# stm_ucboard.net
KiCad netlist of a schematic drawn in EAGLE
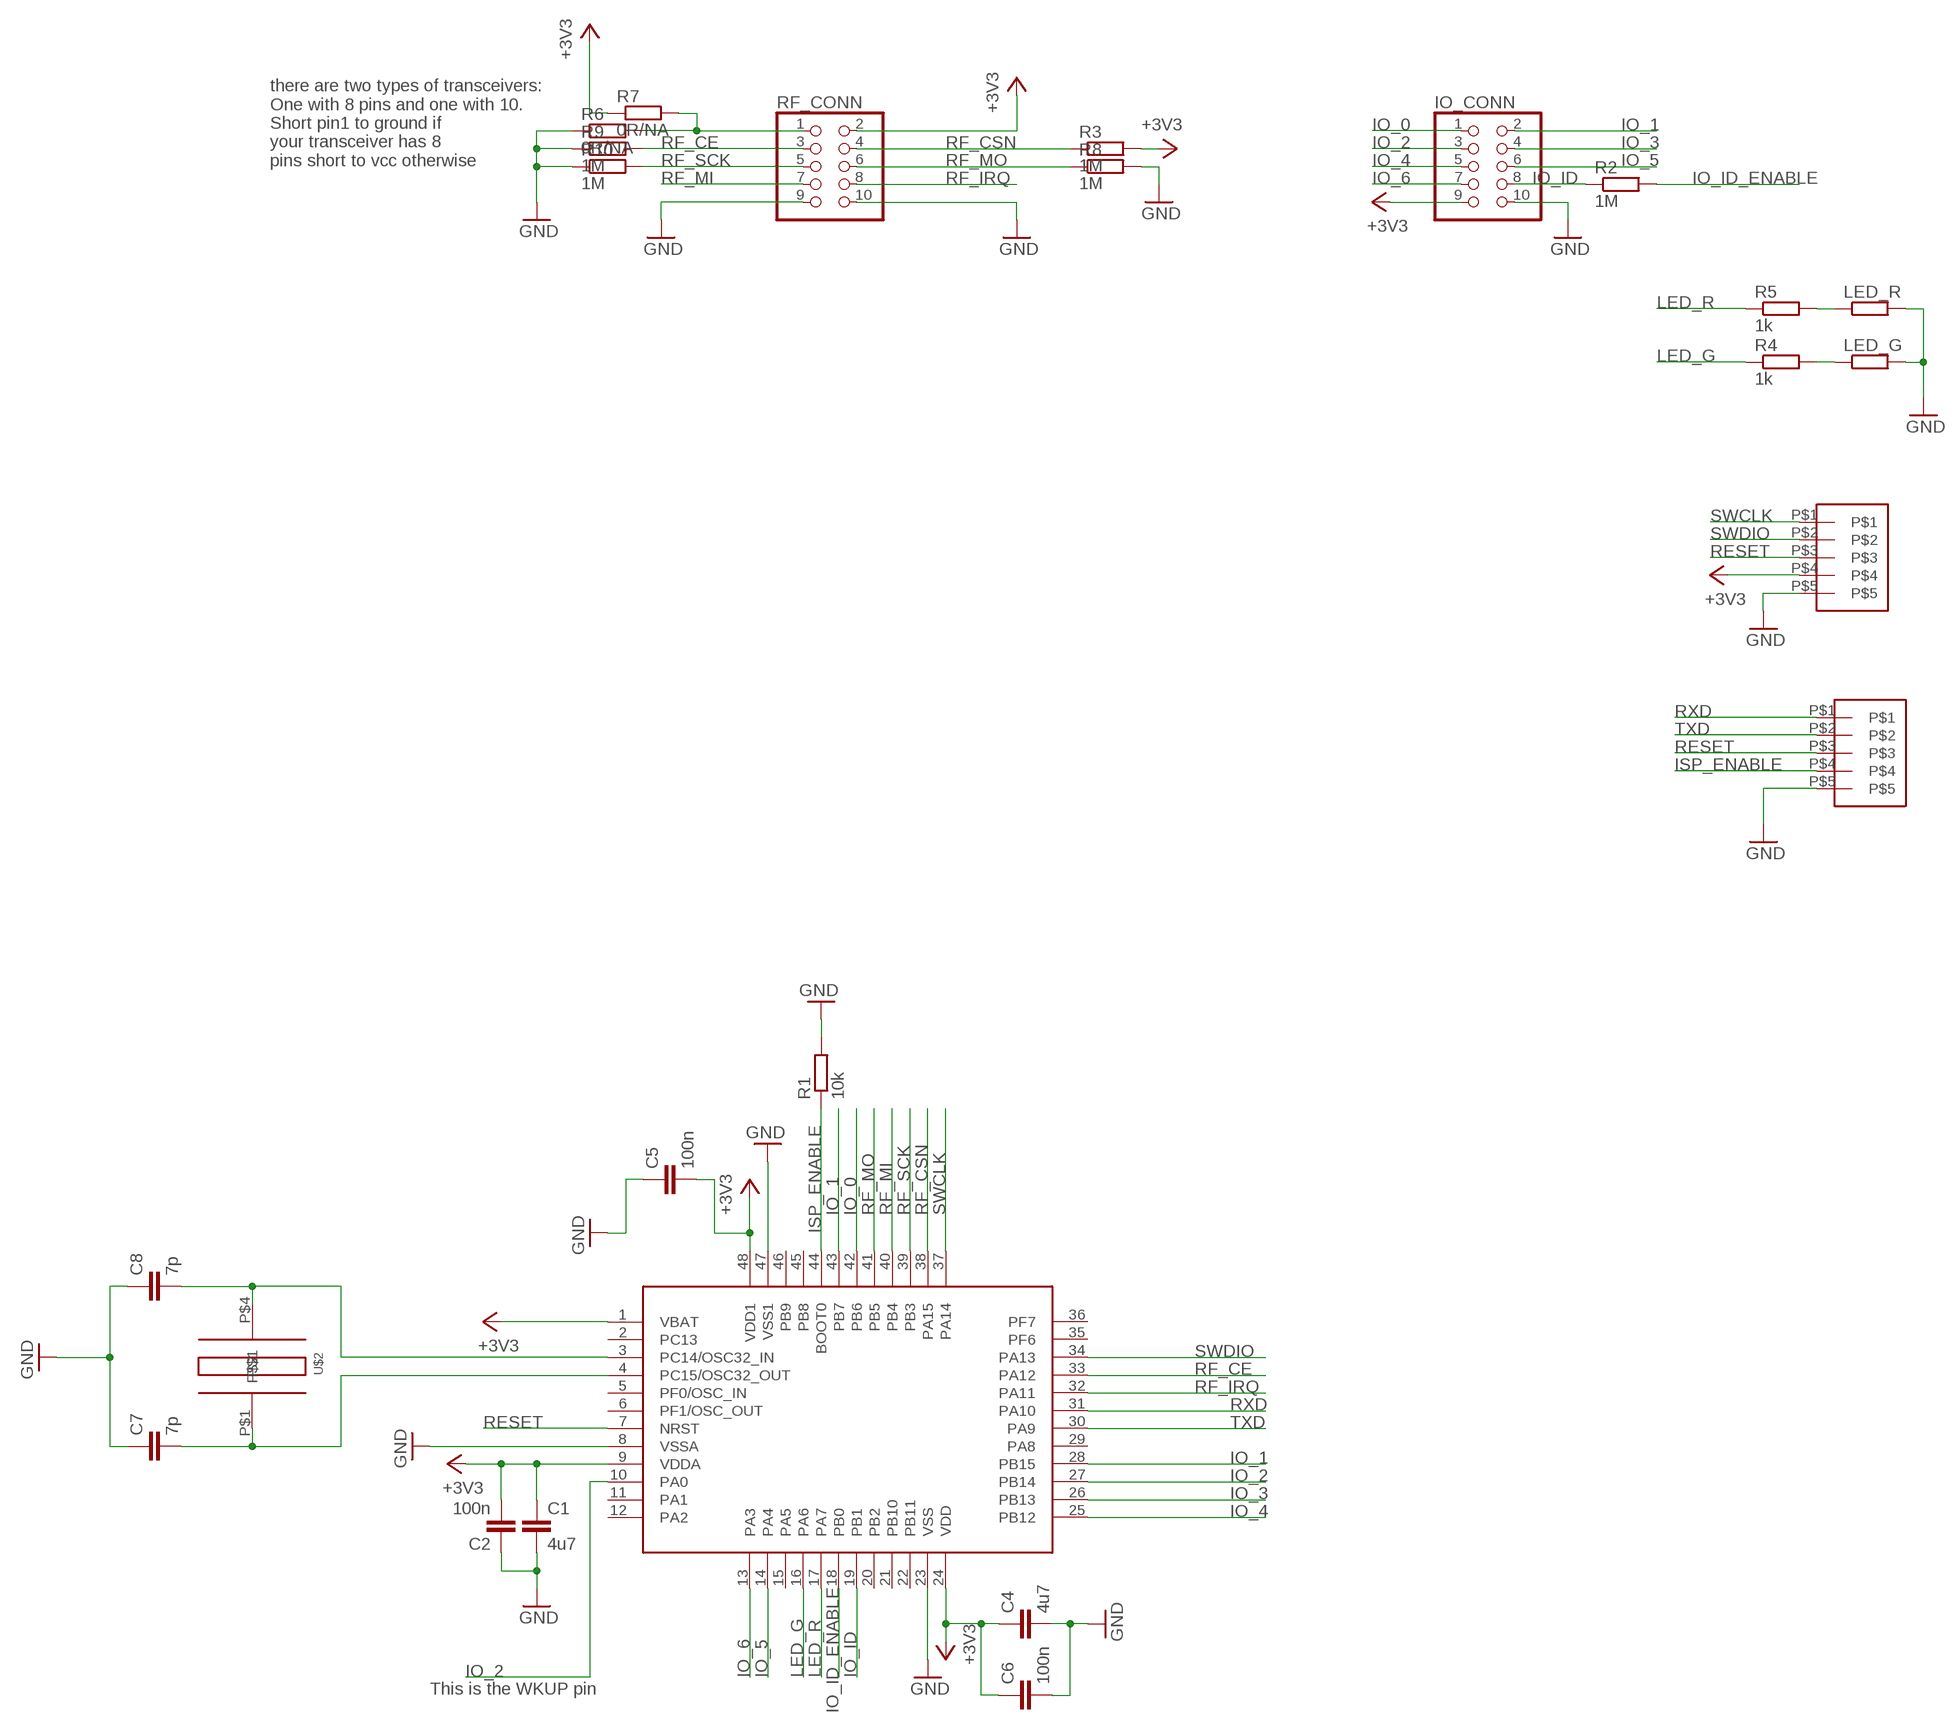
[diagram p0: schematic, sheet 1]

(export (version "E")
  (design (tool "Eeschema 10.0.6"))
  (components
    (comp (ref "C1")
      (value "4u7")
      (footprint "eagle-import:C0603")
      (libsource (lib "eagle-import") (part "C-EUC0603"))
    )
    (comp (ref "C2")
      (value "100n")
      (footprint "eagle-import:C0603")
      (libsource (lib "eagle-import") (part "C-EUC0603"))
    )
    (comp (ref "C4")
      (value "4u7")
      (footprint "eagle-import:C0603")
      (libsource (lib "eagle-import") (part "C-EUC0603"))
    )
    (comp (ref "C5")
      (value "100n")
      (footprint "eagle-import:C0603")
      (libsource (lib "eagle-import") (part "C-EUC0603"))
    )
    (comp (ref "C6")
      (value "100n")
      (footprint "eagle-import:C0603")
      (libsource (lib "eagle-import") (part "C-EUC0603"))
    )
    (comp (ref "C7")
      (value "7p")
      (footprint "eagle-import:C0603")
      (libsource (lib "eagle-import") (part "C-EUC0603"))
    )
    (comp (ref "C8")
      (value "7p")
      (footprint "eagle-import:C0603")
      (libsource (lib "eagle-import") (part "C-EUC0603"))
    )
    (comp (ref "DBG")
      (value "005CONTACTS")
      (footprint "eagle-import:05HEADER")
      (libsource (lib "eagle-import") (part "005CONTACTS"))
    )
    (comp (ref "IO_CONN")
      (value "PINHD-2X5")
      (footprint "eagle-import:2X05")
      (libsource (lib "eagle-import") (part "PINHD-2X5"))
    )
    (comp (ref "LED_G")
      (value "R-EU_R0402")
      (footprint "eagle-import:R0402")
      (libsource (lib "eagle-import") (part "R-EU_R0402"))
    )
    (comp (ref "LED_R")
      (value "R-EU_R0402")
      (footprint "eagle-import:R0402")
      (libsource (lib "eagle-import") (part "R-EU_R0402"))
    )
    (comp (ref "R1")
      (value "10k")
      (footprint "eagle-import:R0402")
      (libsource (lib "eagle-import") (part "R-EU_R0402"))
    )
    (comp (ref "R2")
      (value "1M")
      (footprint "eagle-import:R0402")
      (libsource (lib "eagle-import") (part "R-EU_R0402"))
    )
    (comp (ref "R3")
      (value "1M")
      (footprint "eagle-import:R0402")
      (libsource (lib "eagle-import") (part "R-EU_R0402"))
    )
    (comp (ref "R4")
      (value "1k")
      (footprint "eagle-import:R0402")
      (libsource (lib "eagle-import") (part "R-EU_R0402"))
    )
    (comp (ref "R5")
      (value "1k")
      (footprint "eagle-import:R0402")
      (libsource (lib "eagle-import") (part "R-EU_R0402"))
    )
    (comp (ref "R6")
      (value "0R/NA")
      (footprint "eagle-import:R0201")
      (libsource (lib "eagle-import") (part "R-EU_R0201"))
    )
    (comp (ref "R7")
      (value "0R/NA")
      (footprint "eagle-import:R0201")
      (libsource (lib "eagle-import") (part "R-EU_R0201"))
    )
    (comp (ref "R8")
      (value "1M")
      (footprint "eagle-import:R0402")
      (libsource (lib "eagle-import") (part "R-EU_R0402"))
    )
    (comp (ref "R9")
      (value "1M")
      (footprint "eagle-import:R0402")
      (libsource (lib "eagle-import") (part "R-EU_R0402"))
    )
    (comp (ref "R10")
      (value "1M")
      (footprint "eagle-import:R0402")
      (libsource (lib "eagle-import") (part "R-EU_R0402"))
    )
    (comp (ref "RF_CONN")
      (value "PINHD-2X5")
      (footprint "eagle-import:2X05")
      (libsource (lib "eagle-import") (part "PINHD-2X5"))
    )
    (comp (ref "U$1")
      (value "STM32F051")
      (footprint "eagle-import:LQFP48")
      (libsource (lib "eagle-import") (part "STM32F051"))
    )
    (comp (ref "U$2")
      (value "CRYSTAL_32K")
      (footprint "eagle-import:SOJ4")
      (libsource (lib "eagle-import") (part "CRYSTAL_32K"))
    )
    (comp (ref "UART")
      (value "005CONTACTS")
      (footprint "eagle-import:05HEADER")
      (libsource (lib "eagle-import") (part "005CONTACTS"))
    )
  )
  (nets
    (net (code "1") (name "+3V3") (class "Default")
      (node (ref "C1") (pin "1") (pinfunction "1_1") (pintype "passive"))
      (node (ref "C2") (pin "2") (pinfunction "2_2") (pintype "passive"))
      (node (ref "C4") (pin "1") (pinfunction "1_1") (pintype "passive"))
      (node (ref "C5") (pin "2") (pinfunction "2_2") (pintype "passive"))
      (node (ref "C6") (pin "1") (pinfunction "1_1") (pintype "passive"))
      (node (ref "DBG") (pin "P$4") (pinfunction "P$4_P$4") (pintype "bidirectional"))
      (node (ref "IO_CONN") (pin "9") (pinfunction "9_9") (pintype "passive"))
      (node (ref "R3") (pin "2") (pinfunction "2_2") (pintype "passive"))
      (node (ref "R7") (pin "1") (pinfunction "1_1") (pintype "passive"))
      (node (ref "RF_CONN") (pin "2") (pinfunction "2_2") (pintype "passive"))
      (node (ref "U$1") (pin "1") (pinfunction "VBAT_1") (pintype "bidirectional"))
      (node (ref "U$1") (pin "24") (pinfunction "VDD_24") (pintype "bidirectional"))
      (node (ref "U$1") (pin "48") (pinfunction "VDD1_48") (pintype "bidirectional"))
      (node (ref "U$1") (pin "9") (pinfunction "VDDA_9") (pintype "bidirectional"))
    )
    (net (code "2") (name "/IO_0") (class "Default")
      (node (ref "IO_CONN") (pin "1") (pinfunction "1_1") (pintype "passive"))
      (node (ref "U$1") (pin "42") (pinfunction "PB6_42") (pintype "bidirectional"))
    )
    (net (code "3") (name "/IO_1") (class "Default")
      (node (ref "IO_CONN") (pin "2") (pinfunction "2_2") (pintype "passive"))
      (node (ref "U$1") (pin "28") (pinfunction "PB15_28") (pintype "bidirectional"))
      (node (ref "U$1") (pin "43") (pinfunction "PB7_43") (pintype "bidirectional"))
    )
    (net (code "4") (name "/IO_2") (class "Default")
      (node (ref "IO_CONN") (pin "3") (pinfunction "3_3") (pintype "passive"))
      (node (ref "U$1") (pin "10") (pinfunction "PA0_10") (pintype "bidirectional"))
      (node (ref "U$1") (pin "27") (pinfunction "PB14_27") (pintype "bidirectional"))
    )
    (net (code "5") (name "/IO_3") (class "Default")
      (node (ref "IO_CONN") (pin "4") (pinfunction "4_4") (pintype "passive"))
      (node (ref "U$1") (pin "26") (pinfunction "PB13_26") (pintype "bidirectional"))
    )
    (net (code "6") (name "/IO_4") (class "Default")
      (node (ref "IO_CONN") (pin "5") (pinfunction "5_5") (pintype "passive"))
      (node (ref "U$1") (pin "25") (pinfunction "PB12_25") (pintype "bidirectional"))
    )
    (net (code "7") (name "/IO_5") (class "Default")
      (node (ref "IO_CONN") (pin "6") (pinfunction "6_6") (pintype "passive"))
      (node (ref "U$1") (pin "14") (pinfunction "PA4_14") (pintype "bidirectional"))
    )
    (net (code "8") (name "/IO_6") (class "Default")
      (node (ref "IO_CONN") (pin "7") (pinfunction "7_7") (pintype "passive"))
      (node (ref "U$1") (pin "13") (pinfunction "PA3_13") (pintype "bidirectional"))
    )
    (net (code "9") (name "/IO_ID") (class "Default")
      (node (ref "IO_CONN") (pin "8") (pinfunction "8_8") (pintype "passive"))
      (node (ref "R2") (pin "1") (pinfunction "1_1") (pintype "passive"))
      (node (ref "U$1") (pin "19") (pinfunction "PB1_19") (pintype "bidirectional"))
    )
    (net (code "10") (name "/IO_ID_ENABLE") (class "Default")
      (node (ref "R2") (pin "2") (pinfunction "2_2") (pintype "passive"))
      (node (ref "U$1") (pin "18") (pinfunction "PB0_18") (pintype "bidirectional"))
    )
    (net (code "11") (name "/ISP_ENABLE") (class "Default")
      (node (ref "R1") (pin "1") (pinfunction "1_1") (pintype "passive"))
      (node (ref "U$1") (pin "44") (pinfunction "BOOT0_44") (pintype "bidirectional"))
      (node (ref "UART") (pin "P$4") (pinfunction "P$4_P$4") (pintype "bidirectional"))
    )
    (net (code "12") (name "/LED_G") (class "Default")
      (node (ref "R4") (pin "1") (pinfunction "1_1") (pintype "passive"))
      (node (ref "U$1") (pin "16") (pinfunction "PA6_16") (pintype "bidirectional"))
    )
    (net (code "13") (name "/LED_R") (class "Default")
      (node (ref "R5") (pin "1") (pinfunction "1_1") (pintype "passive"))
      (node (ref "U$1") (pin "17") (pinfunction "PA7_17") (pintype "bidirectional"))
    )
    (net (code "14") (name "/RESET") (class "Default")
      (node (ref "DBG") (pin "P$3") (pinfunction "P$3_P$3") (pintype "bidirectional"))
      (node (ref "U$1") (pin "7") (pinfunction "NRST_7") (pintype "bidirectional"))
      (node (ref "UART") (pin "P$3") (pinfunction "P$3_P$3") (pintype "bidirectional"))
    )
    (net (code "15") (name "/RF_CE") (class "Default")
      (node (ref "R9") (pin "2") (pinfunction "2_2") (pintype "passive"))
      (node (ref "RF_CONN") (pin "3") (pinfunction "3_3") (pintype "passive"))
      (node (ref "U$1") (pin "33") (pinfunction "PA12_33") (pintype "bidirectional"))
    )
    (net (code "16") (name "/RF_CSN") (class "Default")
      (node (ref "R3") (pin "1") (pinfunction "1_1") (pintype "passive"))
      (node (ref "RF_CONN") (pin "4") (pinfunction "4_4") (pintype "passive"))
      (node (ref "U$1") (pin "38") (pinfunction "PA15_38") (pintype "bidirectional"))
    )
    (net (code "17") (name "/RF_IRQ") (class "Default")
      (node (ref "RF_CONN") (pin "8") (pinfunction "8_8") (pintype "passive"))
      (node (ref "U$1") (pin "32") (pinfunction "PA11_32") (pintype "bidirectional"))
    )
    (net (code "18") (name "/RF_MI") (class "Default")
      (node (ref "RF_CONN") (pin "7") (pinfunction "7_7") (pintype "passive"))
      (node (ref "U$1") (pin "40") (pinfunction "PB4_40") (pintype "bidirectional"))
    )
    (net (code "19") (name "/RF_MO") (class "Default")
      (node (ref "R8") (pin "1") (pinfunction "1_1") (pintype "passive"))
      (node (ref "RF_CONN") (pin "6") (pinfunction "6_6") (pintype "passive"))
      (node (ref "U$1") (pin "41") (pinfunction "PB5_41") (pintype "bidirectional"))
    )
    (net (code "20") (name "/RF_SCK") (class "Default")
      (node (ref "R10") (pin "2") (pinfunction "2_2") (pintype "passive"))
      (node (ref "RF_CONN") (pin "5") (pinfunction "5_5") (pintype "passive"))
      (node (ref "U$1") (pin "39") (pinfunction "PB3_39") (pintype "bidirectional"))
    )
    (net (code "21") (name "/RXD") (class "Default")
      (node (ref "U$1") (pin "31") (pinfunction "PA10_31") (pintype "bidirectional"))
      (node (ref "UART") (pin "P$1") (pinfunction "P$1_P$1") (pintype "bidirectional"))
    )
    (net (code "22") (name "/SWCLK") (class "Default")
      (node (ref "DBG") (pin "P$1") (pinfunction "P$1_P$1") (pintype "bidirectional"))
      (node (ref "U$1") (pin "37") (pinfunction "PA14_37") (pintype "bidirectional"))
    )
    (net (code "23") (name "/SWDIO") (class "Default")
      (node (ref "DBG") (pin "P$2") (pinfunction "P$2_P$2") (pintype "bidirectional"))
      (node (ref "U$1") (pin "34") (pinfunction "PA13_34") (pintype "bidirectional"))
    )
    (net (code "24") (name "/TXD") (class "Default")
      (node (ref "U$1") (pin "30") (pinfunction "PA9_30") (pintype "bidirectional"))
      (node (ref "UART") (pin "P$2") (pinfunction "P$2_P$2") (pintype "bidirectional"))
    )
    (net (code "25") (name "GND") (class "Default")
      (node (ref "C1") (pin "2") (pinfunction "2_2") (pintype "passive"))
      (node (ref "C2") (pin "1") (pinfunction "1_1") (pintype "passive"))
      (node (ref "C4") (pin "2") (pinfunction "2_2") (pintype "passive"))
      (node (ref "C5") (pin "1") (pinfunction "1_1") (pintype "passive"))
      (node (ref "C6") (pin "2") (pinfunction "2_2") (pintype "passive"))
      (node (ref "C7") (pin "1") (pinfunction "1_1") (pintype "passive"))
      (node (ref "C8") (pin "1") (pinfunction "1_1") (pintype "passive"))
      (node (ref "DBG") (pin "P$5") (pinfunction "P$5_P$5") (pintype "bidirectional"))
      (node (ref "IO_CONN") (pin "10") (pinfunction "10_10") (pintype "passive"))
      (node (ref "LED_G") (pin "2") (pinfunction "2_2") (pintype "passive"))
      (node (ref "LED_R") (pin "2") (pinfunction "2_2") (pintype "passive"))
      (node (ref "R1") (pin "2") (pinfunction "2_2") (pintype "passive"))
      (node (ref "R10") (pin "1") (pinfunction "1_1") (pintype "passive"))
      (node (ref "R6") (pin "1") (pinfunction "1_1") (pintype "passive"))
      (node (ref "R8") (pin "2") (pinfunction "2_2") (pintype "passive"))
      (node (ref "R9") (pin "1") (pinfunction "1_1") (pintype "passive"))
      (node (ref "RF_CONN") (pin "10") (pinfunction "10_10") (pintype "passive"))
      (node (ref "RF_CONN") (pin "9") (pinfunction "9_9") (pintype "passive"))
      (node (ref "U$1") (pin "23") (pinfunction "VSS_23") (pintype "bidirectional"))
      (node (ref "U$1") (pin "47") (pinfunction "VSS1_47") (pintype "bidirectional"))
      (node (ref "U$1") (pin "8") (pinfunction "VSSA_8") (pintype "bidirectional"))
      (node (ref "UART") (pin "P$5") (pinfunction "P$5_P$5") (pintype "bidirectional"))
    )
    (net (code "26") (name "Net-(LED_G-Pad1)") (class "Default")
      (node (ref "LED_G") (pin "1") (pinfunction "1_1") (pintype "passive"))
      (node (ref "R4") (pin "2") (pinfunction "2_2") (pintype "passive"))
    )
    (net (code "27") (name "Net-(LED_R-Pad1)") (class "Default")
      (node (ref "LED_R") (pin "1") (pinfunction "1_1") (pintype "passive"))
      (node (ref "R5") (pin "2") (pinfunction "2_2") (pintype "passive"))
    )
    (net (code "28") (name "Net-(R6-Pad2)") (class "Default")
      (node (ref "R6") (pin "2") (pinfunction "2_2") (pintype "passive"))
      (node (ref "R7") (pin "2") (pinfunction "2_2") (pintype "passive"))
      (node (ref "RF_CONN") (pin "1") (pinfunction "1_1") (pintype "passive"))
    )
    (net (code "29") (name "Net-(U$1-PC14{slash}OSC32_IN)") (class "Default")
      (node (ref "C8") (pin "2") (pinfunction "2_2") (pintype "passive"))
      (node (ref "U$1") (pin "3") (pinfunction "PC14/OSC32_IN_3") (pintype "bidirectional"))
      (node (ref "U$2") (pin "P$4") (pinfunction "P$2_P$4") (pintype "bidirectional"))
    )
    (net (code "30") (name "Net-(U$1-PC15{slash}OSC32_OUT)") (class "Default")
      (node (ref "C7") (pin "2") (pinfunction "2_2") (pintype "passive"))
      (node (ref "U$1") (pin "4") (pinfunction "PC15/OSC32_OUT_4") (pintype "bidirectional"))
      (node (ref "U$2") (pin "P$1") (pinfunction "P$1_P$1") (pintype "bidirectional"))
    )
    (net (code "31") (name "unconnected-(U$1-PA1-Pad11)") (class "Default")
      (node (ref "U$1") (pin "11") (pinfunction "PA1_11") (pintype "bidirectional"))
    )
    (net (code "32") (name "unconnected-(U$1-PA2-Pad12)") (class "Default")
      (node (ref "U$1") (pin "12") (pinfunction "PA2_12") (pintype "bidirectional"))
    )
    (net (code "33") (name "unconnected-(U$1-PA5-Pad15)") (class "Default")
      (node (ref "U$1") (pin "15") (pinfunction "PA5_15") (pintype "bidirectional"))
    )
    (net (code "34") (name "unconnected-(U$1-PA8-Pad29)") (class "Default")
      (node (ref "U$1") (pin "29") (pinfunction "PA8_29") (pintype "bidirectional"))
    )
    (net (code "35") (name "unconnected-(U$1-PB2-Pad20)") (class "Default")
      (node (ref "U$1") (pin "20") (pinfunction "PB2_20") (pintype "bidirectional"))
    )
    (net (code "36") (name "unconnected-(U$1-PB8-Pad45)") (class "Default")
      (node (ref "U$1") (pin "45") (pinfunction "PB8_45") (pintype "bidirectional"))
    )
    (net (code "37") (name "unconnected-(U$1-PB9-Pad46)") (class "Default")
      (node (ref "U$1") (pin "46") (pinfunction "PB9_46") (pintype "bidirectional"))
    )
    (net (code "38") (name "unconnected-(U$1-PB10-Pad21)") (class "Default")
      (node (ref "U$1") (pin "21") (pinfunction "PB10_21") (pintype "bidirectional"))
    )
    (net (code "39") (name "unconnected-(U$1-PB11-Pad22)") (class "Default")
      (node (ref "U$1") (pin "22") (pinfunction "PB11_22") (pintype "bidirectional"))
    )
    (net (code "40") (name "unconnected-(U$1-PC13-Pad2)") (class "Default")
      (node (ref "U$1") (pin "2") (pinfunction "PC13_2") (pintype "bidirectional"))
    )
    (net (code "41") (name "unconnected-(U$1-PF0{slash}OSC_IN-Pad5)") (class "Default")
      (node (ref "U$1") (pin "5") (pinfunction "PF0/OSC_IN_5") (pintype "bidirectional"))
    )
    (net (code "42") (name "unconnected-(U$1-PF1{slash}OSC_OUT-Pad6)") (class "Default")
      (node (ref "U$1") (pin "6") (pinfunction "PF1/OSC_OUT_6") (pintype "bidirectional"))
    )
    (net (code "43") (name "unconnected-(U$1-PF6-Pad35)") (class "Default")
      (node (ref "U$1") (pin "35") (pinfunction "PF6_35") (pintype "bidirectional"))
    )
    (net (code "44") (name "unconnected-(U$1-PF7-Pad36)") (class "Default")
      (node (ref "U$1") (pin "36") (pinfunction "PF7_36") (pintype "bidirectional"))
    )
  )
)
